# G2G-U_Module.net
KiCad netlist of a schematic drawn in Altium Designer
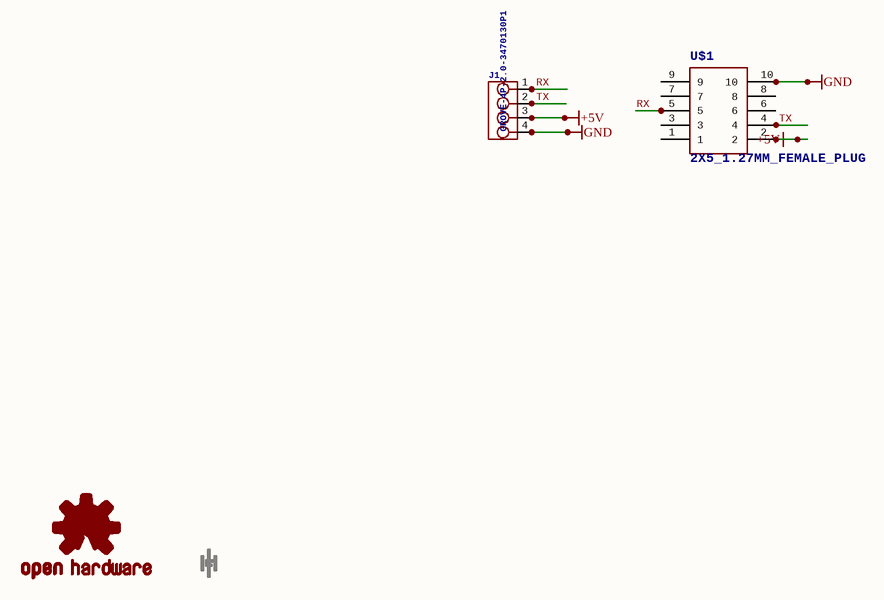
[diagram p0: G2G-U Module.SchDoc]

(export (version "E")
  (design (tool "Eeschema 10.0.6"))
  (components
    (comp (ref "J1")
      (value "GROVE-4P-2.0-3470130P1")
      (footprint "4P-2.0")
      (fields (field (name ">NAME") "J1") (field (name ">VALUE") "GROVE-4P-2.0-3470130P1"))
      (libsource (lib "SoftDust") (part "GROVE-4P-2.0-3470130P1"))
    )
    (comp (ref "LOGO1")
      (value "OSHW-LOGOS")
      (footprint "OSHW-LOGO-S")
      (libsource (lib "SparkFun-Aesthetics") (part "OSHW-LOGOS"))
    )
    (comp (ref "U$1")
      (value "2X5_1.27MM_FEMALE_PLUG")
      (footprint "2X5_1.27MM_FEMALE_PLUG")
      (fields (field (name ">NAME") "U$1") (field (name ">VALUE") "2X5_1.27MM_FEMALE_PLUG"))
      (libsource (lib "SoftDust") (part "2X5_1.27MM_FEMALE_PLUG"))
    )
    (comp (ref "U$2")
      (value "GADGETEER_LOGO_SMALL")
      (footprint "GADGETEER_LOGO_SMALL")
      (libsource (lib "SoftDust") (part "GADGETEER_LOGO_SMALL"))
    )
  )
  (nets
    (net (code "1") (name "+5V") (class "Default")
      (node (ref "J1") (pin "3") (pinfunction "3_3") (pintype "passive"))
      (node (ref "U$1") (pin "2") (pinfunction "2_2") (pintype "passive"))
    )
    (net (code "2") (name "/RX") (class "Default")
      (node (ref "J1") (pin "1") (pinfunction "1_1") (pintype "passive"))
      (node (ref "U$1") (pin "5") (pinfunction "5_5") (pintype "passive"))
    )
    (net (code "3") (name "/TX") (class "Default")
      (node (ref "J1") (pin "2") (pinfunction "2_2") (pintype "passive"))
      (node (ref "U$1") (pin "4") (pinfunction "4_4") (pintype "passive"))
    )
    (net (code "4") (name "GND") (class "Default")
      (node (ref "J1") (pin "4") (pinfunction "4_4") (pintype "passive"))
      (node (ref "U$1") (pin "10") (pinfunction "10_10") (pintype "passive"))
    )
    (net (code "5") (name "unconnected-(U$1-Pad1)") (class "Default")
      (node (ref "U$1") (pin "1") (pinfunction "1_1") (pintype "passive"))
    )
    (net (code "6") (name "unconnected-(U$1-Pad3)") (class "Default")
      (node (ref "U$1") (pin "3") (pinfunction "3_3") (pintype "passive"))
    )
    (net (code "7") (name "unconnected-(U$1-Pad6)") (class "Default")
      (node (ref "U$1") (pin "6") (pinfunction "6_6") (pintype "passive"))
    )
    (net (code "8") (name "unconnected-(U$1-Pad7)") (class "Default")
      (node (ref "U$1") (pin "7") (pinfunction "7_7") (pintype "passive"))
    )
    (net (code "9") (name "unconnected-(U$1-Pad8)") (class "Default")
      (node (ref "U$1") (pin "8") (pinfunction "8_8") (pintype "passive"))
    )
    (net (code "10") (name "unconnected-(U$1-Pad9)") (class "Default")
      (node (ref "U$1") (pin "9") (pinfunction "9_9") (pintype "passive"))
    )
  )
)
